# Display.net
KiCad netlist of a schematic drawn in Altium Designer
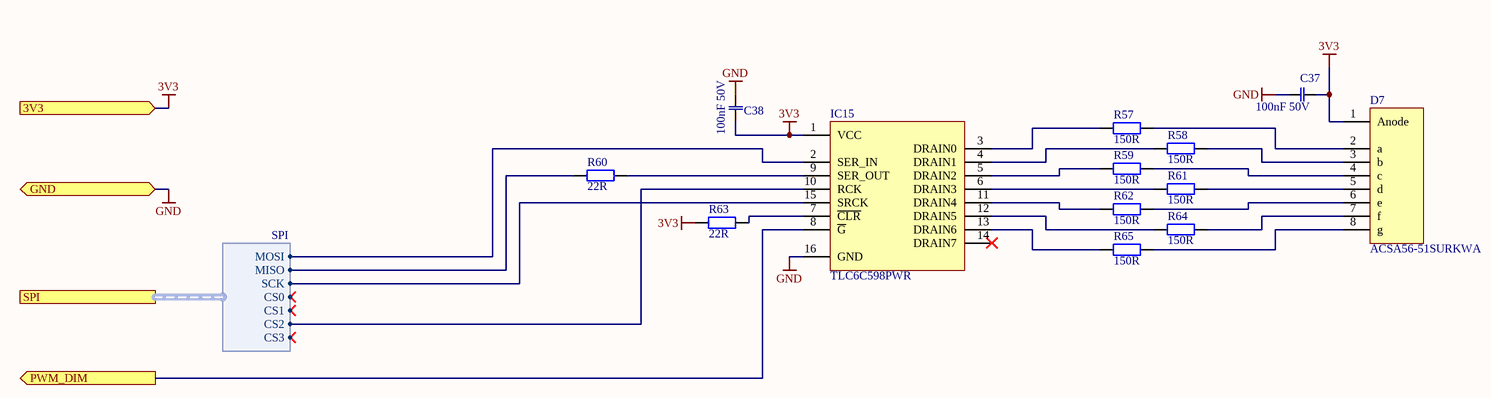
[diagram p0: Display.SchDoc]

(export (version "E")
  (design (tool "Eeschema 10.0.6"))
  (components
    (comp (ref "C37")
      (value "100nF 50V")
      (footprint "CAPC1005N")
      (description "100nF  50V  Ceramic  0402  10%  X7R")
      (fields (field (name "VOLTAGE") "50V") (field (name "MANUFACTURER") "unspecified"))
      (libsource (lib "iMAR Workspace") (part "Kondensator"))
    )
    (comp (ref "C38")
      (value "100nF 50V")
      (footprint "CAPC1005N")
      (description "100nF  50V  Ceramic  0402  10%  X7R")
      (fields (field (name "VOLTAGE") "50V") (field (name "MANUFACTURER") "unspecified"))
      (libsource (lib "iMAR Workspace") (part "Kondensator"))
    )
    (comp (ref "D7")
      (value "ACSA56-51SURKWA")
      (footprint "ACSA56-51SURKWA")
      (description "Smart/Normal 7 Seg Numeric LED Display")
      (fields (field (name "POWER") "75mW") (field (name "MANUFACTURER") "Kingbright"))
      (libsource (lib "iMAR Workspace") (part "7-Segment Anzeige ohne DP"))
    )
    (comp (ref "IC15")
      (value "TLC6C598PWR")
      (footprint "TSSOP65P640X120-16N")
      (description "LED Driver, 8-Segment, PDSO16")
      (fields (field (name "MANUFACTURER") "TEXAS INSTRUMENTS"))
      (libsource (lib "iMAR Workspace") (part "TLC6C598"))
    )
    (comp (ref "R57")
      (value "150R")
      (footprint "RESC1005L")
      (description "150R  0402  62mW  1%  100ppm  50V")
      (fields (field (name "POWER") "62mW") (field (name "VOLTAGE") "50V"))
      (libsource (lib "iMAR Workspace") (part "Widerstand"))
    )
    (comp (ref "R58")
      (value "150R")
      (footprint "RESC1005L")
      (description "150R  0402  62mW  1%  100ppm  50V")
      (fields (field (name "POWER") "62mW") (field (name "VOLTAGE") "50V"))
      (libsource (lib "iMAR Workspace") (part "Widerstand"))
    )
    (comp (ref "R59")
      (value "150R")
      (footprint "RESC1005L")
      (description "150R  0402  62mW  1%  100ppm  50V")
      (fields (field (name "POWER") "62mW") (field (name "VOLTAGE") "50V"))
      (libsource (lib "iMAR Workspace") (part "Widerstand"))
    )
    (comp (ref "R60")
      (value "22R")
      (footprint "RESC1005L")
      (description "22R  0402  62mW  1%  100ppm  50V")
      (fields (field (name "MANUFACTURER") "unspecified") (field (name "POWER") "62mW"))
      (libsource (lib "iMAR Workspace") (part "Widerstand"))
    )
    (comp (ref "R61")
      (value "150R")
      (footprint "RESC1005L")
      (description "150R  0402  62mW  1%  100ppm  50V")
      (fields (field (name "POWER") "62mW") (field (name "VOLTAGE") "50V"))
      (libsource (lib "iMAR Workspace") (part "Widerstand"))
    )
    (comp (ref "R62")
      (value "150R")
      (footprint "RESC1005L")
      (description "150R  0402  62mW  1%  100ppm  50V")
      (fields (field (name "POWER") "62mW") (field (name "VOLTAGE") "50V"))
      (libsource (lib "iMAR Workspace") (part "Widerstand"))
    )
    (comp (ref "R63")
      (value "22R")
      (footprint "RESC1005L")
      (description "22R  0402  62mW  1%  100ppm  50V")
      (fields (field (name "MANUFACTURER") "unspecified") (field (name "POWER") "62mW"))
      (libsource (lib "iMAR Workspace") (part "Widerstand"))
    )
    (comp (ref "R64")
      (value "150R")
      (footprint "RESC1005L")
      (description "150R  0402  62mW  1%  100ppm  50V")
      (fields (field (name "POWER") "62mW") (field (name "VOLTAGE") "50V"))
      (libsource (lib "iMAR Workspace") (part "Widerstand"))
    )
    (comp (ref "R65")
      (value "150R")
      (footprint "RESC1005L")
      (description "150R  0402  62mW  1%  100ppm  50V")
      (fields (field (name "POWER") "62mW") (field (name "VOLTAGE") "50V"))
      (libsource (lib "iMAR Workspace") (part "Widerstand"))
    )
  )
  (nets
    (net (code "2") (name "/CS2") (class "Default")
      (node (ref "IC15") (pin "10") (pinfunction "RCK_10") (pintype "passive"))
    )
    (net (code "3") (name "/MISO") (class "Default")
      (node (ref "R60") (pin "1") (pinfunction "1_1") (pintype "passive"))
    )
    (net (code "4") (name "/MOSI") (class "Default")
      (node (ref "IC15") (pin "2") (pinfunction "SER_IN_2") (pintype "passive"))
    )
    (net (code "5") (name "/PWM_DIM") (class "Default")
      (node (ref "IC15") (pin "8") (pinfunction "~{G}_8") (pintype "passive"))
    )
    (net (code "6") (name "/SCK") (class "Default")
      (node (ref "IC15") (pin "15") (pinfunction "SRCK_15") (pintype "passive"))
    )
    (net (code "8") (name "3V3") (class "Default")
      (node (ref "C37") (pin "1") (pinfunction "1_1") (pintype "passive"))
      (node (ref "C38") (pin "1") (pinfunction "1_1") (pintype "passive"))
      (node (ref "D7") (pin "1") (pinfunction "Anode_1") (pintype "passive"))
      (node (ref "IC15") (pin "1") (pinfunction "VCC_1") (pintype "passive"))
      (node (ref "R63") (pin "1") (pinfunction "1_1") (pintype "passive"))
    )
    (net (code "9") (name "GND") (class "Default")
      (node (ref "C37") (pin "2") (pinfunction "2_2") (pintype "passive"))
      (node (ref "C38") (pin "2") (pinfunction "2_2") (pintype "passive"))
      (node (ref "IC15") (pin "16") (pinfunction "GND_16") (pintype "passive"))
    )
    (net (code "10") (name "Net-(D7-a)") (class "Default")
      (node (ref "D7") (pin "2") (pinfunction "a_2") (pintype "passive"))
      (node (ref "R57") (pin "2") (pinfunction "2_2") (pintype "passive"))
    )
    (net (code "11") (name "Net-(D7-b)") (class "Default")
      (node (ref "D7") (pin "3") (pinfunction "b_3") (pintype "passive"))
      (node (ref "R58") (pin "2") (pinfunction "2_2") (pintype "passive"))
    )
    (net (code "12") (name "Net-(D7-c)") (class "Default")
      (node (ref "D7") (pin "4") (pinfunction "c_4") (pintype "passive"))
      (node (ref "R59") (pin "2") (pinfunction "2_2") (pintype "passive"))
    )
    (net (code "13") (name "Net-(D7-d)") (class "Default")
      (node (ref "D7") (pin "5") (pinfunction "d_5") (pintype "passive"))
      (node (ref "R61") (pin "2") (pinfunction "2_2") (pintype "passive"))
    )
    (net (code "14") (name "Net-(D7-e)") (class "Default")
      (node (ref "D7") (pin "6") (pinfunction "e_6") (pintype "passive"))
      (node (ref "R62") (pin "2") (pinfunction "2_2") (pintype "passive"))
    )
    (net (code "15") (name "Net-(D7-f)") (class "Default")
      (node (ref "D7") (pin "7") (pinfunction "f_7") (pintype "passive"))
      (node (ref "R64") (pin "2") (pinfunction "2_2") (pintype "passive"))
    )
    (net (code "16") (name "Net-(D7-g)") (class "Default")
      (node (ref "D7") (pin "8") (pinfunction "g_8") (pintype "passive"))
      (node (ref "R65") (pin "2") (pinfunction "2_2") (pintype "passive"))
    )
    (net (code "17") (name "Net-(IC15-DRAIN0)") (class "Default")
      (node (ref "IC15") (pin "3") (pinfunction "DRAIN0_3") (pintype "passive"))
      (node (ref "R57") (pin "1") (pinfunction "1_1") (pintype "passive"))
    )
    (net (code "18") (name "Net-(IC15-DRAIN1)") (class "Default")
      (node (ref "IC15") (pin "4") (pinfunction "DRAIN1_4") (pintype "passive"))
      (node (ref "R58") (pin "1") (pinfunction "1_1") (pintype "passive"))
    )
    (net (code "19") (name "Net-(IC15-DRAIN2)") (class "Default")
      (node (ref "IC15") (pin "5") (pinfunction "DRAIN2_5") (pintype "passive"))
      (node (ref "R59") (pin "1") (pinfunction "1_1") (pintype "passive"))
    )
    (net (code "20") (name "Net-(IC15-DRAIN3)") (class "Default")
      (node (ref "IC15") (pin "6") (pinfunction "DRAIN3_6") (pintype "passive"))
      (node (ref "R61") (pin "1") (pinfunction "1_1") (pintype "passive"))
    )
    (net (code "21") (name "Net-(IC15-DRAIN4)") (class "Default")
      (node (ref "IC15") (pin "11") (pinfunction "DRAIN4_11") (pintype "passive"))
      (node (ref "R62") (pin "1") (pinfunction "1_1") (pintype "passive"))
    )
    (net (code "22") (name "Net-(IC15-DRAIN5)") (class "Default")
      (node (ref "IC15") (pin "12") (pinfunction "DRAIN5_12") (pintype "passive"))
      (node (ref "R64") (pin "1") (pinfunction "1_1") (pintype "passive"))
    )
    (net (code "23") (name "Net-(IC15-DRAIN6)") (class "Default")
      (node (ref "IC15") (pin "13") (pinfunction "DRAIN6_13") (pintype "passive"))
      (node (ref "R65") (pin "1") (pinfunction "1_1") (pintype "passive"))
    )
    (net (code "24") (name "Net-(IC15-SER_OUT)") (class "Default")
      (node (ref "IC15") (pin "9") (pinfunction "SER_OUT_9") (pintype "passive"))
      (node (ref "R60") (pin "2") (pinfunction "2_2") (pintype "passive"))
    )
    (net (code "25") (name "Net-(IC15-~{CLR})") (class "Default")
      (node (ref "IC15") (pin "7") (pinfunction "~{CLR}_7") (pintype "passive"))
      (node (ref "R63") (pin "2") (pinfunction "2_2") (pintype "passive"))
    )
    (net (code "26") (name "unconnected-(IC15-DRAIN7-Pad14)") (class "Default")
      (node (ref "IC15") (pin "14") (pinfunction "DRAIN7_14") (pintype "passive+no_connect"))
    )
  )
)
